# Connectors.net
KiCad netlist of a schematic drawn in Altium Designer
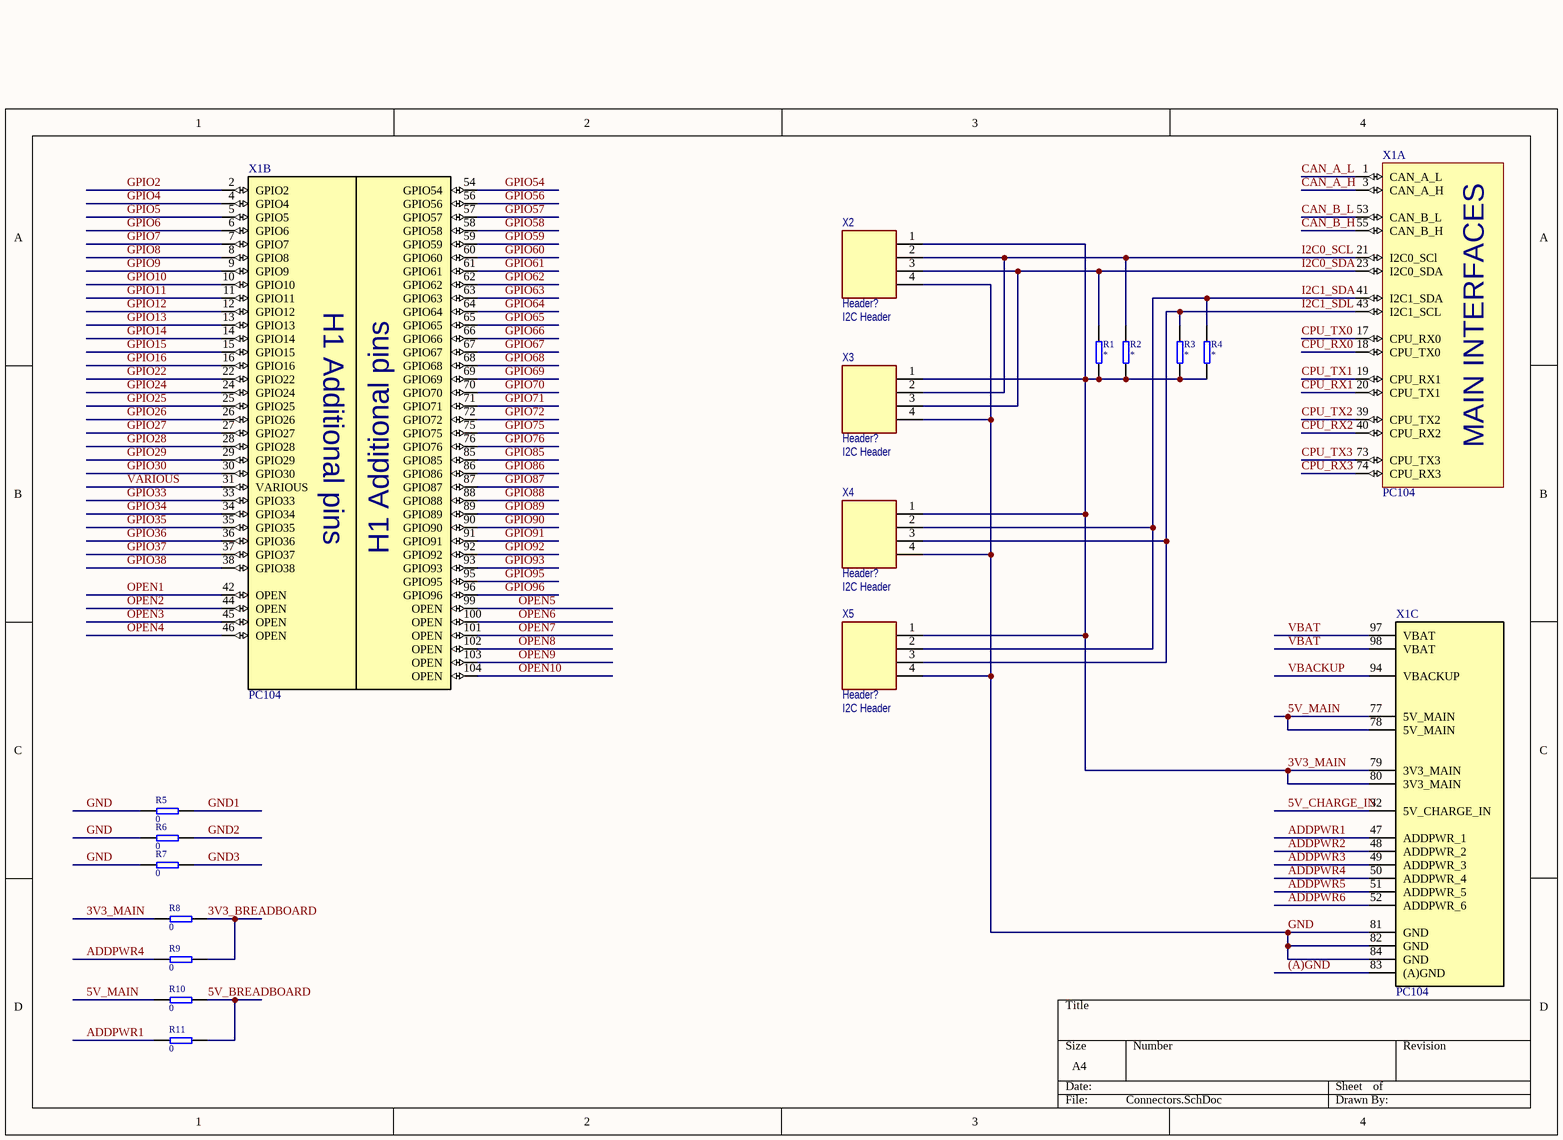
[diagram p0: Connectors.SchDoc]

(export (version "E")
  (design (tool "Eeschema 10.0.6"))
  (components
    (comp (ref "R1")
      (value "RES 0603 *")
      (footprint "RES 0603")
      (description "Resistor")
      (fields (field (name "ALTIUM_VALUE") "*"))
      (libsource (lib "!main") (part "!Resistor"))
    )
    (comp (ref "R2")
      (value "RES 0603 *")
      (footprint "RES 0603")
      (description "Resistor")
      (fields (field (name "ALTIUM_VALUE") "*"))
      (libsource (lib "!main") (part "!Resistor"))
    )
    (comp (ref "R3")
      (value "RES 0603 *")
      (footprint "RES 0603")
      (description "Resistor")
      (fields (field (name "ALTIUM_VALUE") "*"))
      (libsource (lib "!main") (part "!Resistor"))
    )
    (comp (ref "R4")
      (value "RES 0603 *")
      (footprint "RES 0603")
      (description "Resistor")
      (fields (field (name "ALTIUM_VALUE") "*"))
      (libsource (lib "!main") (part "!Resistor"))
    )
    (comp (ref "R5")
      (value "0")
      (footprint "RES 0603")
      (description "Resistor")
      (fields (field (name "Comment") "RES 0603 0"))
      (libsource (lib "!main") (part "!Resistor"))
    )
    (comp (ref "R6")
      (value "0")
      (footprint "RES 0603")
      (description "Resistor")
      (fields (field (name "Comment") "RES 0603 0"))
      (libsource (lib "!main") (part "!Resistor"))
    )
    (comp (ref "R7")
      (value "0")
      (footprint "RES 0603")
      (description "Resistor")
      (fields (field (name "Comment") "RES 0603 0"))
      (libsource (lib "!main") (part "!Resistor"))
    )
    (comp (ref "R8")
      (value "0")
      (footprint "RES 0603")
      (description "Resistor")
      (fields (field (name "Comment") "RES 0603 0"))
      (libsource (lib "!main") (part "!Resistor"))
    )
    (comp (ref "R9")
      (value "0")
      (footprint "RES 0603")
      (description "Resistor")
      (fields (field (name "Comment") "RES 0603 0"))
      (libsource (lib "!main") (part "!Resistor"))
    )
    (comp (ref "R10")
      (value "0")
      (footprint "RES 0603")
      (description "Resistor")
      (fields (field (name "Comment") "RES 0603 0"))
      (libsource (lib "!main") (part "!Resistor"))
    )
    (comp (ref "R11")
      (value "0")
      (footprint "RES 0603")
      (description "Resistor")
      (fields (field (name "Comment") "RES 0603 0"))
      (libsource (lib "!main") (part "!Resistor"))
    )
    (comp (ref "X1")
      (value "PC104")
      (footprint "SI_tmp:PC104_ArianSpace")
      (description "PC104 connector")
      (libsource (lib "SergeyIvlev_tmp") (part "PC104_ArianSpace"))
    )
    (comp (ref "X2")
      (value "Header?")
      (footprint "PicoBlade_4P")
      (description "4x1 header")
      (fields (field (name "PURPOSE") "I2C Header"))
      (libsource (lib "connectors") (part "Header 1x4"))
    )
    (comp (ref "X3")
      (value "Header?")
      (footprint "PicoBlade_4P")
      (description "4x1 header")
      (fields (field (name "PURPOSE") "I2C Header"))
      (libsource (lib "connectors") (part "Header 1x4"))
    )
    (comp (ref "X4")
      (value "Header?")
      (footprint "PicoBlade_4P")
      (description "4x1 header")
      (fields (field (name "PURPOSE") "I2C Header"))
      (libsource (lib "connectors") (part "Header 1x4"))
    )
    (comp (ref "X5")
      (value "Header?")
      (footprint "PicoBlade_4P")
      (description "4x1 header")
      (fields (field (name "PURPOSE") "I2C Header"))
      (libsource (lib "connectors") (part "Header 1x4"))
    )
  )
  (nets
    (net (code "1") (name "/(A)GND") (class "Default")
      (node (ref "X1") (pin "83") (pinfunction "(A)GND_83") (pintype "power_in"))
    )
    (net (code "2") (name "/3V3_BREADBOARD") (class "Default")
      (node (ref "R8") (pin "2") (pinfunction "12_2") (pintype "passive"))
      (node (ref "R9") (pin "2") (pinfunction "12_2") (pintype "passive"))
    )
    (net (code "3") (name "/3V3_MAIN") (class "Default")
      (node (ref "R1") (pin "2") (pinfunction "12_2") (pintype "passive"))
      (node (ref "R2") (pin "1") (pinfunction "11_1") (pintype "passive"))
      (node (ref "R3") (pin "1") (pinfunction "11_1") (pintype "passive"))
      (node (ref "R4") (pin "1") (pinfunction "11_1") (pintype "passive"))
      (node (ref "R8") (pin "1") (pinfunction "11_1") (pintype "passive"))
      (node (ref "X1") (pin "79") (pinfunction "3V3_MAIN_79") (pintype "power_in"))
      (node (ref "X1") (pin "80") (pinfunction "3V3_MAIN_80") (pintype "power_in"))
      (node (ref "X2") (pin "1") (pinfunction "10_1") (pintype "passive"))
      (node (ref "X3") (pin "1") (pinfunction "10_1") (pintype "passive"))
      (node (ref "X4") (pin "1") (pinfunction "10_1") (pintype "passive"))
      (node (ref "X5") (pin "1") (pinfunction "10_1") (pintype "passive"))
    )
    (net (code "4") (name "/5V_BREADBOARD") (class "Default")
      (node (ref "R10") (pin "2") (pinfunction "12_2") (pintype "passive"))
      (node (ref "R11") (pin "2") (pinfunction "12_2") (pintype "passive"))
    )
    (net (code "5") (name "/5V_CHARGE_IN") (class "Default")
      (node (ref "X1") (pin "32") (pinfunction "5V_CHARGE_IN_32") (pintype "power_in"))
    )
    (net (code "6") (name "/5V_MAIN") (class "Default")
      (node (ref "R10") (pin "1") (pinfunction "11_1") (pintype "passive"))
      (node (ref "X1") (pin "77") (pinfunction "5V_MAIN_77") (pintype "power_in"))
      (node (ref "X1") (pin "78") (pinfunction "5V_MAIN_78") (pintype "power_in"))
    )
    (net (code "7") (name "/ADDPWR1") (class "Default")
      (node (ref "R11") (pin "1") (pinfunction "11_1") (pintype "passive"))
      (node (ref "X1") (pin "47") (pinfunction "ADDPWR_1_47") (pintype "power_in"))
    )
    (net (code "8") (name "/ADDPWR2") (class "Default")
      (node (ref "X1") (pin "48") (pinfunction "ADDPWR_2_48") (pintype "power_in"))
    )
    (net (code "9") (name "/ADDPWR3") (class "Default")
      (node (ref "X1") (pin "49") (pinfunction "ADDPWR_3_49") (pintype "power_in"))
    )
    (net (code "10") (name "/ADDPWR4") (class "Default")
      (node (ref "R9") (pin "1") (pinfunction "11_1") (pintype "passive"))
      (node (ref "X1") (pin "50") (pinfunction "ADDPWR_4_50") (pintype "power_in"))
    )
    (net (code "11") (name "/ADDPWR5") (class "Default")
      (node (ref "X1") (pin "51") (pinfunction "ADDPWR_5_51") (pintype "power_in"))
    )
    (net (code "12") (name "/ADDPWR6") (class "Default")
      (node (ref "X1") (pin "52") (pinfunction "ADDPWR_6_52") (pintype "power_in"))
    )
    (net (code "13") (name "/CAN_A_H") (class "Default")
      (node (ref "X1") (pin "3") (pinfunction "CAN_A_H_3") (pintype "bidirectional"))
    )
    (net (code "14") (name "/CAN_A_L") (class "Default")
      (node (ref "X1") (pin "1") (pinfunction "CAN_A_L_1") (pintype "bidirectional"))
    )
    (net (code "15") (name "/CAN_B_H") (class "Default")
      (node (ref "X1") (pin "55") (pinfunction "CAN_B_H_55") (pintype "bidirectional"))
    )
    (net (code "16") (name "/CAN_B_L") (class "Default")
      (node (ref "X1") (pin "53") (pinfunction "CAN_B_L_53") (pintype "bidirectional"))
    )
    (net (code "17") (name "/CPU_RX0") (class "Default")
      (node (ref "X1") (pin "18") (pinfunction "CPU_TX0_18") (pintype "bidirectional"))
    )
    (net (code "18") (name "/CPU_RX1") (class "Default")
      (node (ref "X1") (pin "20") (pinfunction "CPU_TX1_20") (pintype "bidirectional"))
    )
    (net (code "19") (name "/CPU_RX2") (class "Default")
      (node (ref "X1") (pin "40") (pinfunction "CPU_RX2_40") (pintype "bidirectional"))
    )
    (net (code "20") (name "/CPU_RX3") (class "Default")
      (node (ref "X1") (pin "74") (pinfunction "CPU_RX3_74") (pintype "bidirectional"))
    )
    (net (code "21") (name "/CPU_TX0") (class "Default")
      (node (ref "X1") (pin "17") (pinfunction "CPU_RX0_17") (pintype "bidirectional"))
    )
    (net (code "22") (name "/CPU_TX1") (class "Default")
      (node (ref "X1") (pin "19") (pinfunction "CPU_RX1_19") (pintype "bidirectional"))
    )
    (net (code "23") (name "/CPU_TX2") (class "Default")
      (node (ref "X1") (pin "39") (pinfunction "CPU_TX2_39") (pintype "bidirectional"))
    )
    (net (code "24") (name "/CPU_TX3") (class "Default")
      (node (ref "X1") (pin "73") (pinfunction "CPU_TX3_73") (pintype "bidirectional"))
    )
    (net (code "25") (name "/GND") (class "Default")
      (node (ref "R5") (pin "1") (pinfunction "11_1") (pintype "passive"))
      (node (ref "R6") (pin "1") (pinfunction "11_1") (pintype "passive"))
      (node (ref "R7") (pin "1") (pinfunction "11_1") (pintype "passive"))
      (node (ref "X1") (pin "81") (pinfunction "GND_81") (pintype "power_in"))
      (node (ref "X1") (pin "82") (pinfunction "GND_82") (pintype "power_in"))
      (node (ref "X1") (pin "84") (pinfunction "GND_84") (pintype "power_in"))
      (node (ref "X2") (pin "4") (pinfunction "13_4") (pintype "passive"))
      (node (ref "X3") (pin "4") (pinfunction "13_4") (pintype "passive"))
      (node (ref "X4") (pin "4") (pinfunction "13_4") (pintype "passive"))
      (node (ref "X5") (pin "4") (pinfunction "13_4") (pintype "passive"))
    )
    (net (code "26") (name "/GND1") (class "Default")
      (node (ref "R5") (pin "2") (pinfunction "12_2") (pintype "passive"))
    )
    (net (code "27") (name "/GND2") (class "Default")
      (node (ref "R6") (pin "2") (pinfunction "12_2") (pintype "passive"))
    )
    (net (code "28") (name "/GND3") (class "Default")
      (node (ref "R7") (pin "2") (pinfunction "12_2") (pintype "passive"))
    )
    (net (code "29") (name "/GPIO2") (class "Default")
      (node (ref "X1") (pin "2") (pinfunction "GPIO2_2") (pintype "bidirectional"))
    )
    (net (code "30") (name "/GPIO4") (class "Default")
      (node (ref "X1") (pin "4") (pinfunction "GPIO4_4") (pintype "bidirectional"))
    )
    (net (code "31") (name "/GPIO5") (class "Default")
      (node (ref "X1") (pin "5") (pinfunction "GPIO5_5") (pintype "bidirectional"))
    )
    (net (code "32") (name "/GPIO6") (class "Default")
      (node (ref "X1") (pin "6") (pinfunction "GPIO6_6") (pintype "bidirectional"))
    )
    (net (code "33") (name "/GPIO7") (class "Default")
      (node (ref "X1") (pin "7") (pinfunction "GPIO7_7") (pintype "bidirectional"))
    )
    (net (code "34") (name "/GPIO8") (class "Default")
      (node (ref "X1") (pin "8") (pinfunction "GPIO8_8") (pintype "bidirectional"))
    )
    (net (code "35") (name "/GPIO9") (class "Default")
      (node (ref "X1") (pin "9") (pinfunction "GPIO9_9") (pintype "bidirectional"))
    )
    (net (code "36") (name "/GPIO10") (class "Default")
      (node (ref "X1") (pin "10") (pinfunction "GPIO10_10") (pintype "bidirectional"))
    )
    (net (code "37") (name "/GPIO11") (class "Default")
      (node (ref "X1") (pin "11") (pinfunction "GPIO11_11") (pintype "bidirectional"))
    )
    (net (code "38") (name "/GPIO12") (class "Default")
      (node (ref "X1") (pin "12") (pinfunction "GPIO12_12") (pintype "bidirectional"))
    )
    (net (code "39") (name "/GPIO13") (class "Default")
      (node (ref "X1") (pin "13") (pinfunction "GPIO13_13") (pintype "bidirectional"))
    )
    (net (code "40") (name "/GPIO14") (class "Default")
      (node (ref "X1") (pin "14") (pinfunction "GPIO14_14") (pintype "bidirectional"))
    )
    (net (code "41") (name "/GPIO15") (class "Default")
      (node (ref "X1") (pin "15") (pinfunction "GPIO15_15") (pintype "bidirectional"))
    )
    (net (code "42") (name "/GPIO16") (class "Default")
      (node (ref "X1") (pin "16") (pinfunction "GPIO16_16") (pintype "bidirectional"))
    )
    (net (code "43") (name "/GPIO22") (class "Default")
      (node (ref "X1") (pin "22") (pinfunction "GPIO22_22") (pintype "bidirectional"))
    )
    (net (code "44") (name "/GPIO24") (class "Default")
      (node (ref "X1") (pin "24") (pinfunction "GPIO24_24") (pintype "bidirectional"))
    )
    (net (code "45") (name "/GPIO25") (class "Default")
      (node (ref "X1") (pin "25") (pinfunction "GPIO25_25") (pintype "bidirectional"))
    )
    (net (code "46") (name "/GPIO26") (class "Default")
      (node (ref "X1") (pin "26") (pinfunction "GPIO26_26") (pintype "bidirectional"))
    )
    (net (code "47") (name "/GPIO27") (class "Default")
      (node (ref "X1") (pin "27") (pinfunction "GPIO27_27") (pintype "bidirectional"))
    )
    (net (code "48") (name "/GPIO28") (class "Default")
      (node (ref "X1") (pin "28") (pinfunction "GPIO28_28") (pintype "bidirectional"))
    )
    (net (code "49") (name "/GPIO29") (class "Default")
      (node (ref "X1") (pin "29") (pinfunction "GPIO29_29") (pintype "bidirectional"))
    )
    (net (code "50") (name "/GPIO30") (class "Default")
      (node (ref "X1") (pin "30") (pinfunction "GPIO30_30") (pintype "bidirectional"))
    )
    (net (code "51") (name "/GPIO33") (class "Default")
      (node (ref "X1") (pin "33") (pinfunction "GPIO33_33") (pintype "bidirectional"))
    )
    (net (code "52") (name "/GPIO34") (class "Default")
      (node (ref "X1") (pin "34") (pinfunction "GPIO34_34") (pintype "bidirectional"))
    )
    (net (code "53") (name "/GPIO35") (class "Default")
      (node (ref "X1") (pin "35") (pinfunction "GPIO35_35") (pintype "bidirectional"))
    )
    (net (code "54") (name "/GPIO36") (class "Default")
      (node (ref "X1") (pin "36") (pinfunction "GPIO36_36") (pintype "bidirectional"))
    )
    (net (code "55") (name "/GPIO37") (class "Default")
      (node (ref "X1") (pin "37") (pinfunction "GPIO37_37") (pintype "bidirectional"))
    )
    (net (code "56") (name "/GPIO38") (class "Default")
      (node (ref "X1") (pin "38") (pinfunction "GPIO38_38") (pintype "bidirectional"))
    )
    (net (code "57") (name "/GPIO54") (class "Default")
      (node (ref "X1") (pin "54") (pinfunction "GPIO54_54") (pintype "bidirectional"))
    )
    (net (code "58") (name "/GPIO56") (class "Default")
      (node (ref "X1") (pin "56") (pinfunction "GPIO56_56") (pintype "bidirectional"))
    )
    (net (code "59") (name "/GPIO57") (class "Default")
      (node (ref "X1") (pin "57") (pinfunction "GPIO57_57") (pintype "bidirectional"))
    )
    (net (code "60") (name "/GPIO58") (class "Default")
      (node (ref "X1") (pin "58") (pinfunction "GPIO58_58") (pintype "bidirectional"))
    )
    (net (code "61") (name "/GPIO59") (class "Default")
      (node (ref "X1") (pin "59") (pinfunction "GPIO59_59") (pintype "bidirectional"))
    )
    (net (code "62") (name "/GPIO60") (class "Default")
      (node (ref "X1") (pin "60") (pinfunction "GPIO60_60") (pintype "bidirectional"))
    )
    (net (code "63") (name "/GPIO61") (class "Default")
      (node (ref "X1") (pin "61") (pinfunction "GPIO61_61") (pintype "bidirectional"))
    )
    (net (code "64") (name "/GPIO62") (class "Default")
      (node (ref "X1") (pin "62") (pinfunction "GPIO62_62") (pintype "bidirectional"))
    )
    (net (code "65") (name "/GPIO63") (class "Default")
      (node (ref "X1") (pin "63") (pinfunction "GPIO63_63") (pintype "bidirectional"))
    )
    (net (code "66") (name "/GPIO64") (class "Default")
      (node (ref "X1") (pin "64") (pinfunction "GPIO64_64") (pintype "bidirectional"))
    )
    (net (code "67") (name "/GPIO65") (class "Default")
      (node (ref "X1") (pin "65") (pinfunction "GPIO65_65") (pintype "bidirectional"))
    )
    (net (code "68") (name "/GPIO66") (class "Default")
      (node (ref "X1") (pin "66") (pinfunction "GPIO66_66") (pintype "bidirectional"))
    )
    (net (code "69") (name "/GPIO67") (class "Default")
      (node (ref "X1") (pin "67") (pinfunction "GPIO67_67") (pintype "bidirectional"))
    )
    (net (code "70") (name "/GPIO68") (class "Default")
      (node (ref "X1") (pin "68") (pinfunction "GPIO68_68") (pintype "bidirectional"))
    )
    (net (code "71") (name "/GPIO69") (class "Default")
      (node (ref "X1") (pin "69") (pinfunction "GPIO69_69") (pintype "bidirectional"))
    )
    (net (code "72") (name "/GPIO70") (class "Default")
      (node (ref "X1") (pin "70") (pinfunction "GPIO70_70") (pintype "bidirectional"))
    )
    (net (code "73") (name "/GPIO71") (class "Default")
      (node (ref "X1") (pin "71") (pinfunction "GPIO71_71") (pintype "bidirectional"))
    )
    (net (code "74") (name "/GPIO72") (class "Default")
      (node (ref "X1") (pin "72") (pinfunction "GPIO72_72") (pintype "bidirectional"))
    )
    (net (code "75") (name "/GPIO75") (class "Default")
      (node (ref "X1") (pin "75") (pinfunction "GPIO75_75") (pintype "bidirectional"))
    )
    (net (code "76") (name "/GPIO76") (class "Default")
      (node (ref "X1") (pin "76") (pinfunction "GPIO76_76") (pintype "bidirectional"))
    )
    (net (code "77") (name "/GPIO85") (class "Default")
      (node (ref "X1") (pin "85") (pinfunction "GPIO85_85") (pintype "bidirectional"))
    )
    (net (code "78") (name "/GPIO86") (class "Default")
      (node (ref "X1") (pin "86") (pinfunction "GPIO86_86") (pintype "bidirectional"))
    )
    (net (code "79") (name "/GPIO87") (class "Default")
      (node (ref "X1") (pin "87") (pinfunction "GPIO87_87") (pintype "bidirectional"))
    )
    (net (code "80") (name "/GPIO88") (class "Default")
      (node (ref "X1") (pin "88") (pinfunction "GPIO88_88") (pintype "bidirectional"))
    )
    (net (code "81") (name "/GPIO89") (class "Default")
      (node (ref "X1") (pin "89") (pinfunction "GPIO89_89") (pintype "bidirectional"))
    )
    (net (code "82") (name "/GPIO90") (class "Default")
      (node (ref "X1") (pin "90") (pinfunction "GPIO90_90") (pintype "bidirectional"))
    )
    (net (code "83") (name "/GPIO91") (class "Default")
      (node (ref "X1") (pin "91") (pinfunction "GPIO91_91") (pintype "bidirectional"))
    )
    (net (code "84") (name "/GPIO92") (class "Default")
      (node (ref "X1") (pin "92") (pinfunction "GPIO92_92") (pintype "bidirectional"))
    )
    (net (code "85") (name "/GPIO93") (class "Default")
      (node (ref "X1") (pin "93") (pinfunction "GPIO93_93") (pintype "bidirectional"))
    )
    (net (code "86") (name "/GPIO95") (class "Default")
      (node (ref "X1") (pin "95") (pinfunction "GPIO95_95") (pintype "bidirectional"))
    )
    (net (code "87") (name "/GPIO96") (class "Default")
      (node (ref "X1") (pin "96") (pinfunction "GPIO96_96") (pintype "bidirectional"))
    )
    (net (code "88") (name "/I2C0_SCL") (class "Default")
      (node (ref "R2") (pin "2") (pinfunction "12_2") (pintype "passive"))
      (node (ref "X1") (pin "21") (pinfunction "I2C0_SCl_21") (pintype "bidirectional"))
      (node (ref "X2") (pin "2") (pinfunction "11_2") (pintype "passive"))
      (node (ref "X3") (pin "2") (pinfunction "11_2") (pintype "passive"))
    )
    (net (code "89") (name "/I2C0_SDA") (class "Default")
      (node (ref "R1") (pin "1") (pinfunction "11_1") (pintype "passive"))
      (node (ref "X1") (pin "23") (pinfunction "I2C0_SDA_23") (pintype "bidirectional"))
      (node (ref "X2") (pin "3") (pinfunction "12_3") (pintype "passive"))
      (node (ref "X3") (pin "3") (pinfunction "12_3") (pintype "passive"))
    )
    (net (code "90") (name "/I2C1_SDA") (class "Default")
      (node (ref "R4") (pin "2") (pinfunction "12_2") (pintype "passive"))
      (node (ref "X1") (pin "41") (pinfunction "I2C1_SDA_41") (pintype "bidirectional"))
      (node (ref "X4") (pin "2") (pinfunction "11_2") (pintype "passive"))
      (node (ref "X5") (pin "2") (pinfunction "11_2") (pintype "passive"))
    )
    (net (code "91") (name "/I2C1_SDL") (class "Default")
      (node (ref "R3") (pin "2") (pinfunction "12_2") (pintype "passive"))
      (node (ref "X1") (pin "43") (pinfunction "I2C1_SCL_43") (pintype "bidirectional"))
      (node (ref "X4") (pin "3") (pinfunction "12_3") (pintype "passive"))
      (node (ref "X5") (pin "3") (pinfunction "12_3") (pintype "passive"))
    )
    (net (code "92") (name "/OPEN1") (class "Default")
      (node (ref "X1") (pin "42") (pinfunction "OPEN_42") (pintype "bidirectional"))
    )
    (net (code "93") (name "/OPEN2") (class "Default")
      (node (ref "X1") (pin "44") (pinfunction "OPEN_44") (pintype "bidirectional"))
    )
    (net (code "94") (name "/OPEN3") (class "Default")
      (node (ref "X1") (pin "45") (pinfunction "OPEN_45") (pintype "bidirectional"))
    )
    (net (code "95") (name "/OPEN4") (class "Default")
      (node (ref "X1") (pin "46") (pinfunction "OPEN_46") (pintype "bidirectional"))
    )
    (net (code "96") (name "/OPEN5") (class "Default")
      (node (ref "X1") (pin "99") (pinfunction "OPEN_99") (pintype "bidirectional"))
    )
    (net (code "97") (name "/OPEN6") (class "Default")
      (node (ref "X1") (pin "100") (pinfunction "OPEN_100") (pintype "bidirectional"))
    )
    (net (code "98") (name "/OPEN7") (class "Default")
      (node (ref "X1") (pin "101") (pinfunction "OPEN_101") (pintype "bidirectional"))
    )
    (net (code "99") (name "/OPEN8") (class "Default")
      (node (ref "X1") (pin "102") (pinfunction "OPEN_102") (pintype "bidirectional"))
    )
    (net (code "100") (name "/OPEN9") (class "Default")
      (node (ref "X1") (pin "103") (pinfunction "OPEN_103") (pintype "bidirectional"))
    )
    (net (code "101") (name "/OPEN10") (class "Default")
      (node (ref "X1") (pin "104") (pinfunction "OPEN_104") (pintype "bidirectional"))
    )
    (net (code "102") (name "/VARIOUS") (class "Default")
      (node (ref "X1") (pin "31") (pinfunction "VARIOUS_31") (pintype "bidirectional"))
    )
    (net (code "103") (name "/VBACKUP") (class "Default")
      (node (ref "X1") (pin "94") (pinfunction "VBACKUP_94") (pintype "power_in"))
    )
    (net (code "104") (name "/VBAT") (class "Default")
      (node (ref "X1") (pin "97") (pinfunction "VBAT_97") (pintype "power_in"))
      (node (ref "X1") (pin "98") (pinfunction "VBAT_98") (pintype "power_in"))
    )
  )
)
